# main_board.net
KiCad netlist of a schematic drawn in EAGLE
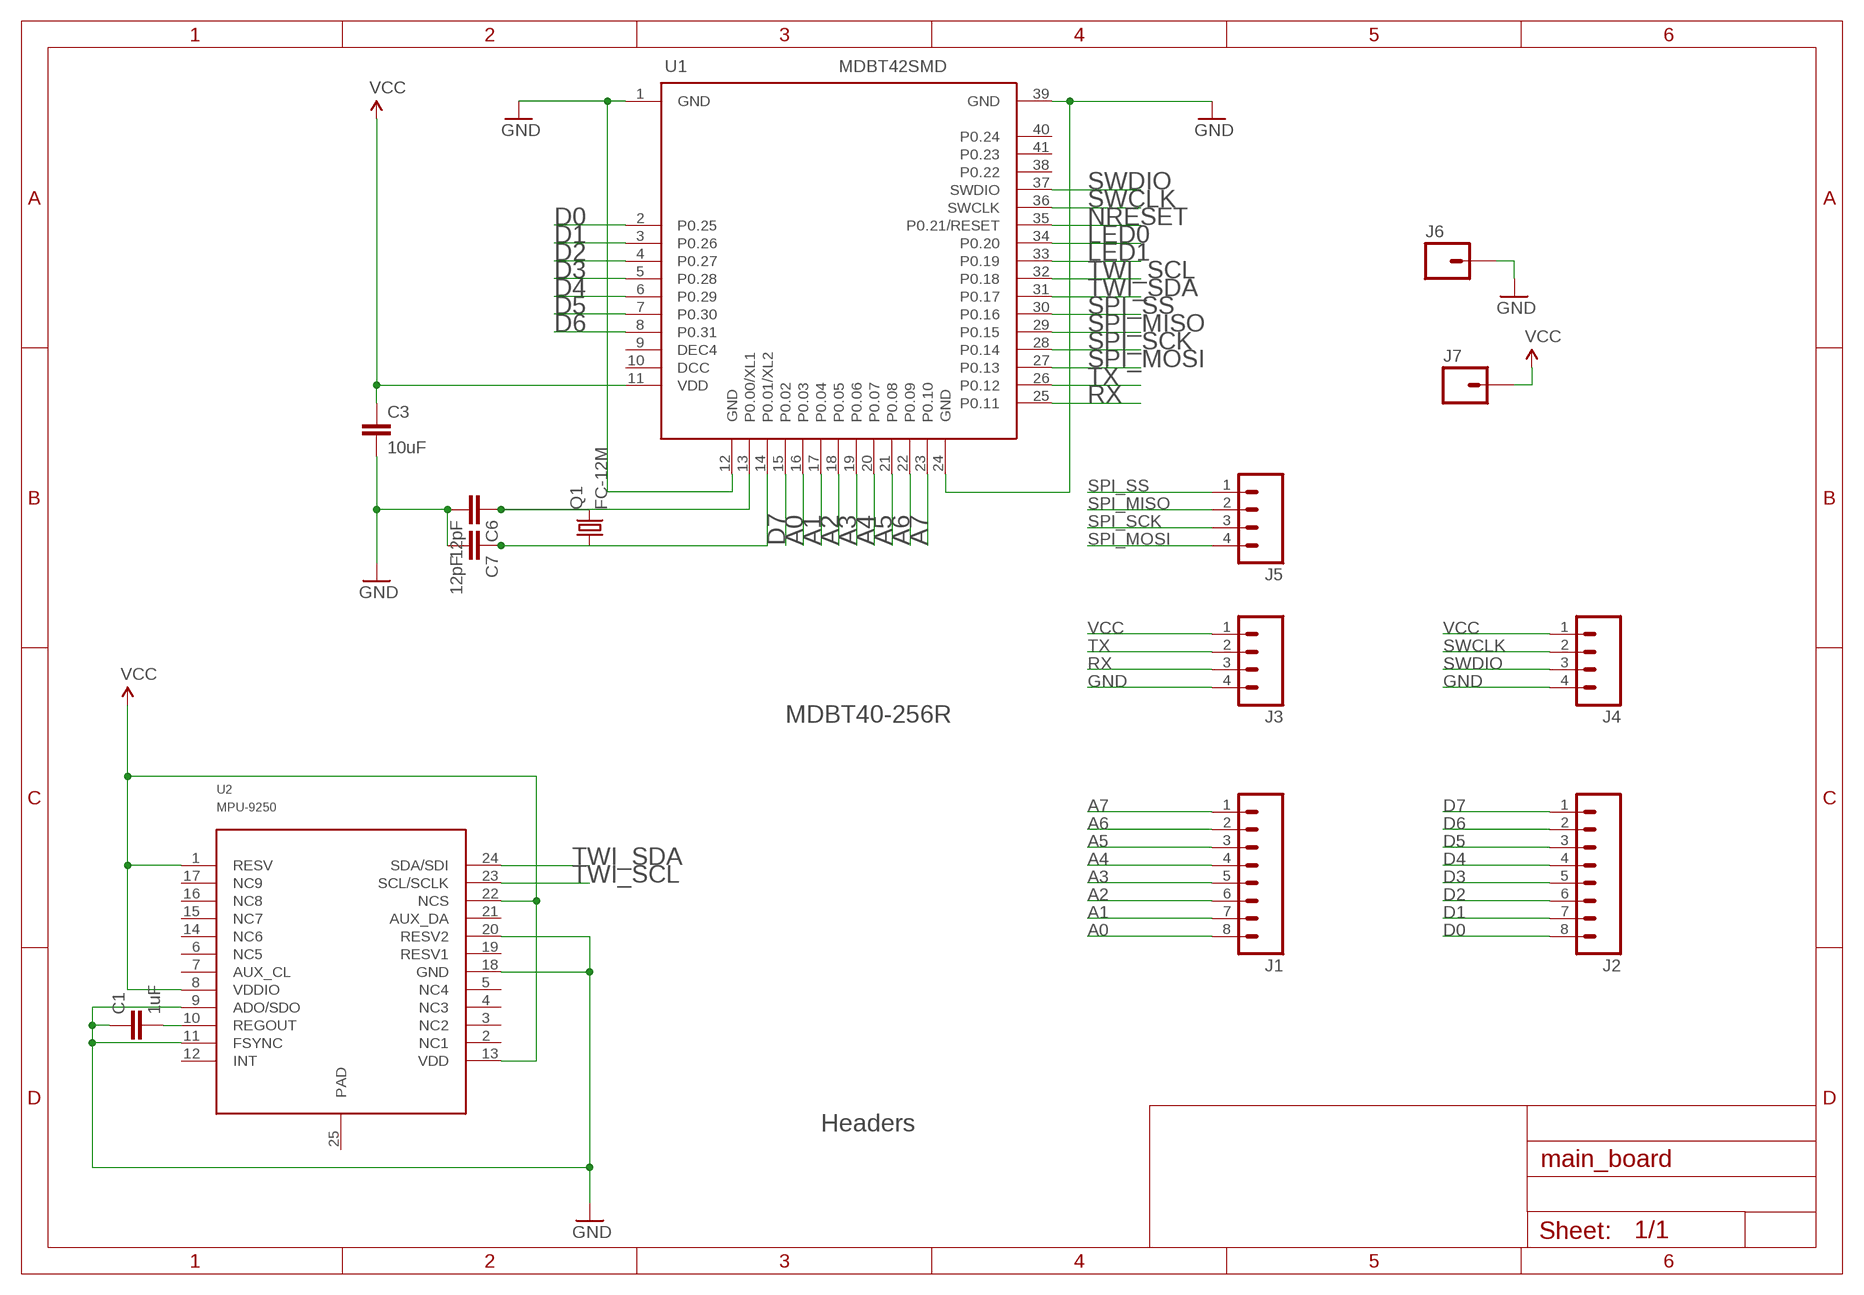
[diagram p0: schematic, sheet 1]

(export (version "E")
  (design (tool "Eeschema 10.0.6"))
  (components
    (comp (ref "C1")
      (value "1uF")
      (footprint "eagle-import:0603-CAP")
      (libsource (lib "eagle-import") (part "CAP0603-CAP"))
    )
    (comp (ref "C3")
      (value "10uF")
      (footprint "eagle-import:0603-CAP")
      (libsource (lib "eagle-import") (part "CAP0603-CAP"))
    )
    (comp (ref "C6")
      (value "12pF")
      (footprint "eagle-import:0603-CAP")
      (libsource (lib "eagle-import") (part "CAP0603-CAP"))
    )
    (comp (ref "C7")
      (value "12pF")
      (footprint "eagle-import:0603-CAP")
      (libsource (lib "eagle-import") (part "CAP0603-CAP"))
    )
    (comp (ref "J1")
      (value "M08SILK_FEMALE_PTH")
      (footprint "eagle-import:1X08")
      (libsource (lib "eagle-import") (part "M08SILK_FEMALE_PTH"))
    )
    (comp (ref "J2")
      (value "M08SILK_FEMALE_PTH")
      (footprint "eagle-import:1X08")
      (libsource (lib "eagle-import") (part "M08SILK_FEMALE_PTH"))
    )
    (comp (ref "J3")
      (value "M04PTH")
      (footprint "eagle-import:1X04")
      (libsource (lib "eagle-import") (part "M04PTH"))
    )
    (comp (ref "J4")
      (value "M04PTH")
      (footprint "eagle-import:1X04")
      (libsource (lib "eagle-import") (part "M04PTH"))
    )
    (comp (ref "J5")
      (value "M04PTH")
      (footprint "eagle-import:1X04")
      (libsource (lib "eagle-import") (part "M04PTH"))
    )
    (comp (ref "J6")
      (value "M01_SMDSMD_4X2")
      (footprint "eagle-import:1X01_SMD")
      (libsource (lib "eagle-import") (part "M01_SMDSMD_4X2"))
    )
    (comp (ref "J7")
      (value "M01_SMDSMD_4X2")
      (footprint "eagle-import:1X01_SMD")
      (libsource (lib "eagle-import") (part "M01_SMDSMD_4X2"))
    )
    (comp (ref "Q1")
      (value "FC-12M")
      (footprint "eagle-import:FC-12M")
      (libsource (lib "eagle-import") (part "FC-12M"))
    )
    (comp (ref "U1")
      (value "MDBT42SMD")
      (footprint "eagle-import:MDBT42")
      (libsource (lib "eagle-import") (part "MDBT42SMD"))
    )
    (comp (ref "U2")
      (value "MPU-9250")
      (footprint "eagle-import:LEAD-QFN24")
      (libsource (lib "eagle-import") (part "MPU-9250"))
    )
  )
  (nets
    (net (code "1") (name "/A0") (class "Default")
      (node (ref "J1") (pin "8") (pinfunction "8_8") (pintype "passive"))
      (node (ref "U1") (pin "16") (pinfunction "P0.03_16") (pintype "bidirectional"))
    )
    (net (code "2") (name "/A1") (class "Default")
      (node (ref "J1") (pin "7") (pinfunction "7_7") (pintype "passive"))
      (node (ref "U1") (pin "17") (pinfunction "P0.04_17") (pintype "bidirectional"))
    )
    (net (code "3") (name "/A2") (class "Default")
      (node (ref "J1") (pin "6") (pinfunction "6_6") (pintype "passive"))
      (node (ref "U1") (pin "18") (pinfunction "P0.05_18") (pintype "bidirectional"))
    )
    (net (code "4") (name "/A3") (class "Default")
      (node (ref "J1") (pin "5") (pinfunction "5_5") (pintype "passive"))
      (node (ref "U1") (pin "19") (pinfunction "P0.06_19") (pintype "bidirectional"))
    )
    (net (code "5") (name "/A4") (class "Default")
      (node (ref "J1") (pin "4") (pinfunction "4_4") (pintype "passive"))
      (node (ref "U1") (pin "20") (pinfunction "P0.07_20") (pintype "bidirectional"))
    )
    (net (code "6") (name "/A5") (class "Default")
      (node (ref "J1") (pin "3") (pinfunction "3_3") (pintype "passive"))
      (node (ref "U1") (pin "21") (pinfunction "P0.08_21") (pintype "bidirectional"))
    )
    (net (code "7") (name "/A6") (class "Default")
      (node (ref "J1") (pin "2") (pinfunction "2_2") (pintype "passive"))
      (node (ref "U1") (pin "22") (pinfunction "P0.09_22") (pintype "bidirectional"))
    )
    (net (code "8") (name "/A7") (class "Default")
      (node (ref "J1") (pin "1") (pinfunction "1_1") (pintype "passive"))
      (node (ref "U1") (pin "23") (pinfunction "P0.10_23") (pintype "bidirectional"))
    )
    (net (code "9") (name "/D0") (class "Default")
      (node (ref "J2") (pin "8") (pinfunction "8_8") (pintype "passive"))
      (node (ref "U1") (pin "2") (pinfunction "P0.25_2") (pintype "bidirectional"))
    )
    (net (code "10") (name "/D1") (class "Default")
      (node (ref "J2") (pin "7") (pinfunction "7_7") (pintype "passive"))
      (node (ref "U1") (pin "3") (pinfunction "P0.26_3") (pintype "bidirectional"))
    )
    (net (code "11") (name "/D2") (class "Default")
      (node (ref "J2") (pin "6") (pinfunction "6_6") (pintype "passive"))
      (node (ref "U1") (pin "4") (pinfunction "P0.27_4") (pintype "bidirectional"))
    )
    (net (code "12") (name "/D3") (class "Default")
      (node (ref "J2") (pin "5") (pinfunction "5_5") (pintype "passive"))
      (node (ref "U1") (pin "5") (pinfunction "P0.28_5") (pintype "bidirectional"))
    )
    (net (code "13") (name "/D4") (class "Default")
      (node (ref "J2") (pin "4") (pinfunction "4_4") (pintype "passive"))
      (node (ref "U1") (pin "6") (pinfunction "P0.29_6") (pintype "bidirectional"))
    )
    (net (code "14") (name "/D5") (class "Default")
      (node (ref "J2") (pin "3") (pinfunction "3_3") (pintype "passive"))
      (node (ref "U1") (pin "7") (pinfunction "P0.30_7") (pintype "bidirectional"))
    )
    (net (code "15") (name "/D6") (class "Default")
      (node (ref "J2") (pin "2") (pinfunction "2_2") (pintype "passive"))
      (node (ref "U1") (pin "8") (pinfunction "P0.31_8") (pintype "bidirectional"))
    )
    (net (code "16") (name "/D7") (class "Default")
      (node (ref "J2") (pin "1") (pinfunction "1_1") (pintype "passive"))
      (node (ref "U1") (pin "15") (pinfunction "P0.02_15") (pintype "bidirectional"))
    )
    (net (code "17") (name "/LED0") (class "Default")
      (node (ref "U1") (pin "34") (pinfunction "P0.20_34") (pintype "bidirectional"))
    )
    (net (code "18") (name "/LED1") (class "Default")
      (node (ref "U1") (pin "33") (pinfunction "P0.19_33") (pintype "bidirectional"))
    )
    (net (code "19") (name "/NRESET") (class "Default")
      (node (ref "U1") (pin "35") (pinfunction "P0.21/RESET_35") (pintype "bidirectional"))
    )
    (net (code "20") (name "/RX") (class "Default")
      (node (ref "J3") (pin "3") (pinfunction "3_3") (pintype "passive"))
      (node (ref "U1") (pin "25") (pinfunction "P0.11_25") (pintype "bidirectional"))
    )
    (net (code "21") (name "/SPI_MISO") (class "Default")
      (node (ref "J5") (pin "2") (pinfunction "2_2") (pintype "passive"))
      (node (ref "U1") (pin "29") (pinfunction "P0.15_29") (pintype "bidirectional"))
    )
    (net (code "22") (name "/SPI_MOSI") (class "Default")
      (node (ref "J5") (pin "4") (pinfunction "4_4") (pintype "passive"))
      (node (ref "U1") (pin "27") (pinfunction "P0.13_27") (pintype "bidirectional"))
    )
    (net (code "23") (name "/SPI_SCK") (class "Default")
      (node (ref "J5") (pin "3") (pinfunction "3_3") (pintype "passive"))
      (node (ref "U1") (pin "28") (pinfunction "P0.14_28") (pintype "bidirectional"))
    )
    (net (code "24") (name "/SPI_SS") (class "Default")
      (node (ref "J5") (pin "1") (pinfunction "1_1") (pintype "passive"))
      (node (ref "U1") (pin "30") (pinfunction "P0.16_30") (pintype "bidirectional"))
    )
    (net (code "25") (name "/SWCLK") (class "Default")
      (node (ref "J4") (pin "2") (pinfunction "2_2") (pintype "passive"))
      (node (ref "U1") (pin "36") (pinfunction "SWCLK_36") (pintype "bidirectional"))
    )
    (net (code "26") (name "/SWDIO") (class "Default")
      (node (ref "J4") (pin "3") (pinfunction "3_3") (pintype "passive"))
      (node (ref "U1") (pin "37") (pinfunction "SWDIO_37") (pintype "bidirectional"))
    )
    (net (code "27") (name "/TWI_SCL") (class "Default")
      (node (ref "U1") (pin "32") (pinfunction "P0.18_32") (pintype "bidirectional"))
      (node (ref "U2") (pin "23") (pinfunction "SCL/SCLK_23") (pintype "bidirectional"))
    )
    (net (code "28") (name "/TWI_SDA") (class "Default")
      (node (ref "U1") (pin "31") (pinfunction "P0.17_31") (pintype "bidirectional"))
      (node (ref "U2") (pin "24") (pinfunction "SDA/SDI_24") (pintype "bidirectional"))
    )
    (net (code "29") (name "/TX") (class "Default")
      (node (ref "J3") (pin "2") (pinfunction "2_2") (pintype "passive"))
      (node (ref "U1") (pin "26") (pinfunction "P0.12_26") (pintype "bidirectional"))
    )
    (net (code "30") (name "GND") (class "Default")
      (node (ref "C1") (pin "1") (pinfunction "1_1") (pintype "passive"))
      (node (ref "C3") (pin "2") (pinfunction "2_2") (pintype "passive"))
      (node (ref "C6") (pin "2") (pinfunction "2_2") (pintype "passive"))
      (node (ref "C7") (pin "2") (pinfunction "2_2") (pintype "passive"))
      (node (ref "J3") (pin "4") (pinfunction "4_4") (pintype "passive"))
      (node (ref "J4") (pin "4") (pinfunction "4_4") (pintype "passive"))
      (node (ref "J6") (pin "P$1") (pinfunction "1_P$1") (pintype "passive"))
      (node (ref "U1") (pin "1") (pinfunction "GND_1") (pintype "bidirectional"))
      (node (ref "U1") (pin "12") (pinfunction "GND_12") (pintype "bidirectional"))
      (node (ref "U1") (pin "24") (pinfunction "GND_24") (pintype "bidirectional"))
      (node (ref "U1") (pin "39") (pinfunction "GND_39") (pintype "bidirectional"))
      (node (ref "U2") (pin "11") (pinfunction "FSYNC_11") (pintype "bidirectional"))
      (node (ref "U2") (pin "18") (pinfunction "GND_18") (pintype "bidirectional"))
      (node (ref "U2") (pin "20") (pinfunction "RESV2_20") (pintype "bidirectional"))
      (node (ref "U2") (pin "9") (pinfunction "ADO/SDO_9") (pintype "bidirectional"))
    )
    (net (code "31") (name "Net-(U1-P0.00{slash}XL1)") (class "Default")
      (node (ref "C6") (pin "1") (pinfunction "1_1") (pintype "passive"))
      (node (ref "Q1") (pin "2") (pinfunction "2_2") (pintype "passive"))
      (node (ref "U1") (pin "13") (pinfunction "P0.00/XL1_13") (pintype "bidirectional"))
    )
    (net (code "32") (name "Net-(U1-P0.01{slash}XL2)") (class "Default")
      (node (ref "C7") (pin "1") (pinfunction "1_1") (pintype "passive"))
      (node (ref "Q1") (pin "1") (pinfunction "1_1") (pintype "passive"))
      (node (ref "U1") (pin "14") (pinfunction "P0.01/XL2_14") (pintype "bidirectional"))
    )
    (net (code "33") (name "Net-(U2-REGOUT)") (class "Default")
      (node (ref "C1") (pin "2") (pinfunction "2_2") (pintype "passive"))
      (node (ref "U2") (pin "10") (pinfunction "REGOUT_10") (pintype "bidirectional"))
    )
    (net (code "34") (name "VCC") (class "Default")
      (node (ref "C3") (pin "1") (pinfunction "1_1") (pintype "passive"))
      (node (ref "J3") (pin "1") (pinfunction "1_1") (pintype "passive"))
      (node (ref "J4") (pin "1") (pinfunction "1_1") (pintype "passive"))
      (node (ref "J7") (pin "P$1") (pinfunction "1_P$1") (pintype "passive"))
      (node (ref "U1") (pin "11") (pinfunction "VDD_11") (pintype "bidirectional"))
      (node (ref "U2") (pin "1") (pinfunction "RESV_1") (pintype "bidirectional"))
      (node (ref "U2") (pin "13") (pinfunction "VDD_13") (pintype "bidirectional"))
      (node (ref "U2") (pin "22") (pinfunction "NCS_22") (pintype "bidirectional"))
      (node (ref "U2") (pin "8") (pinfunction "VDDIO_8") (pintype "bidirectional"))
    )
    (net (code "35") (name "unconnected-(U1-DCC-Pad10)") (class "Default")
      (node (ref "U1") (pin "10") (pinfunction "DCC_10") (pintype "bidirectional"))
    )
    (net (code "36") (name "unconnected-(U1-DEC4-Pad9)") (class "Default")
      (node (ref "U1") (pin "9") (pinfunction "DEC4_9") (pintype "bidirectional"))
    )
    (net (code "37") (name "unconnected-(U1-P0.22-Pad38)") (class "Default")
      (node (ref "U1") (pin "38") (pinfunction "P0.22_38") (pintype "bidirectional"))
    )
    (net (code "38") (name "unconnected-(U1-P0.23-Pad41)") (class "Default")
      (node (ref "U1") (pin "41") (pinfunction "P0.23_41") (pintype "bidirectional"))
    )
    (net (code "39") (name "unconnected-(U1-P0.24-Pad40)") (class "Default")
      (node (ref "U1") (pin "40") (pinfunction "P0.24_40") (pintype "bidirectional"))
    )
    (net (code "40") (name "unconnected-(U2-AUX_CL-Pad7)") (class "Default")
      (node (ref "U2") (pin "7") (pinfunction "AUX_CL_7") (pintype "bidirectional"))
    )
    (net (code "41") (name "unconnected-(U2-AUX_DA-Pad21)") (class "Default")
      (node (ref "U2") (pin "21") (pinfunction "AUX_DA_21") (pintype "bidirectional"))
    )
    (net (code "42") (name "unconnected-(U2-INT-Pad12)") (class "Default")
      (node (ref "U2") (pin "12") (pinfunction "INT_12") (pintype "bidirectional"))
    )
    (net (code "43") (name "unconnected-(U2-NC1-Pad2)") (class "Default")
      (node (ref "U2") (pin "2") (pinfunction "NC1_2") (pintype "bidirectional"))
    )
    (net (code "44") (name "unconnected-(U2-NC2-Pad3)") (class "Default")
      (node (ref "U2") (pin "3") (pinfunction "NC2_3") (pintype "bidirectional"))
    )
    (net (code "45") (name "unconnected-(U2-NC3-Pad4)") (class "Default")
      (node (ref "U2") (pin "4") (pinfunction "NC3_4") (pintype "bidirectional"))
    )
    (net (code "46") (name "unconnected-(U2-NC4-Pad5)") (class "Default")
      (node (ref "U2") (pin "5") (pinfunction "NC4_5") (pintype "bidirectional"))
    )
    (net (code "47") (name "unconnected-(U2-NC5-Pad6)") (class "Default")
      (node (ref "U2") (pin "6") (pinfunction "NC5_6") (pintype "bidirectional"))
    )
    (net (code "48") (name "unconnected-(U2-NC6-Pad14)") (class "Default")
      (node (ref "U2") (pin "14") (pinfunction "NC6_14") (pintype "bidirectional"))
    )
    (net (code "49") (name "unconnected-(U2-NC7-Pad15)") (class "Default")
      (node (ref "U2") (pin "15") (pinfunction "NC7_15") (pintype "bidirectional"))
    )
    (net (code "50") (name "unconnected-(U2-NC8-Pad16)") (class "Default")
      (node (ref "U2") (pin "16") (pinfunction "NC8_16") (pintype "bidirectional"))
    )
    (net (code "51") (name "unconnected-(U2-NC9-Pad17)") (class "Default")
      (node (ref "U2") (pin "17") (pinfunction "NC9_17") (pintype "bidirectional"))
    )
    (net (code "52") (name "unconnected-(U2-PAD-Pad25)") (class "Default")
      (node (ref "U2") (pin "25") (pinfunction "PAD_25") (pintype "bidirectional"))
    )
    (net (code "53") (name "unconnected-(U2-RESV1-Pad19)") (class "Default")
      (node (ref "U2") (pin "19") (pinfunction "RESV1_19") (pintype "bidirectional"))
    )
  )
)
